# 02_HMS_BW16.net
KiCad netlist of a schematic drawn in Altium Designer
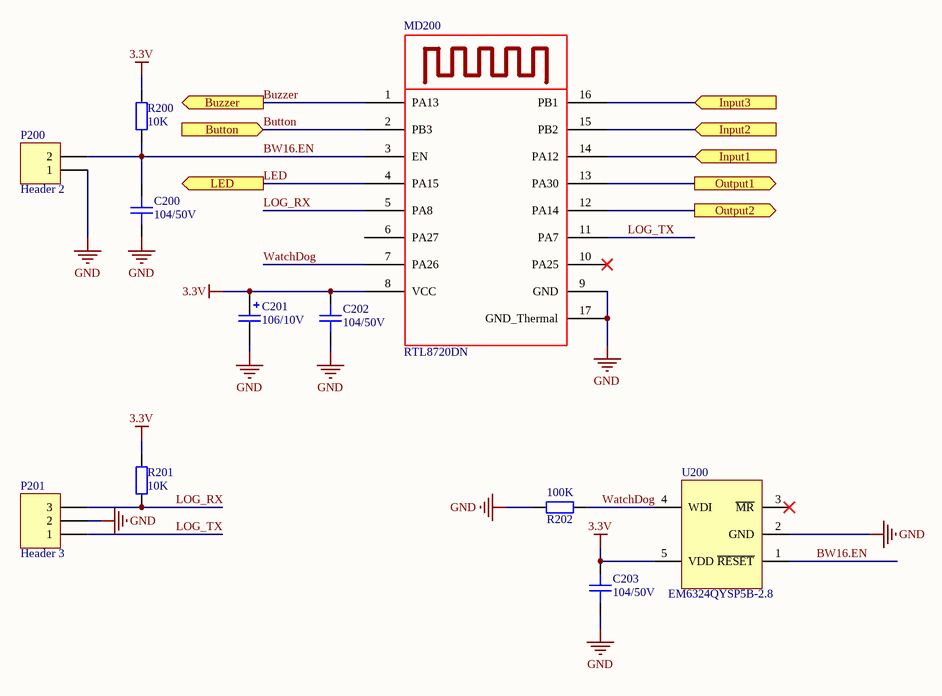
[diagram p0: [02].HMS.BW16.SchDoc]

(export (version "E")
  (design (tool "Eeschema 10.0.6"))
  (components
    (comp (ref "C200")
      (value "104/50V")
      (footprint "CAP_CERAMIC_0402(1005)")
      (description "CAP CER 0.1UF 50V X5R 0402")
      (fields (field (name "MPN") "CC0402KRX5R9BB104") (field (name "MFR") "YAGEO"))
      (libsource (lib "01.Capacitor.0402") (part "CC0402KRX5R9BB104"))
    )
    (comp (ref "C201")
      (value "106/10V")
      (footprint "CAP_TANTAL_1206(3216-18)")
      (description "CAP Tantal 10uF/6.3V 10% 1206")
      (fields (field (name "MPN") "293D106X96R3A2TE3") (field (name "MFR") "KYOCERA AVX Componenis"))
      (libsource (lib "01.Capacitor") (part "TAJC107K010RNJ"))
    )
    (comp (ref "C202")
      (value "104/50V")
      (footprint "CAP_CERAMIC_0402(1005)")
      (description "CAP CER 0.1UF 50V X5R 0402")
      (fields (field (name "MPN") "CC0402KRX5R9BB104") (field (name "MFR") "YAGEO"))
      (libsource (lib "01.Capacitor.0402") (part "CC0402KRX5R9BB104"))
    )
    (comp (ref "C203")
      (value "104/50V")
      (footprint "CAP_CERAMIC_0402(1005)")
      (description "CAP CER 0.1UF 50V X5R 0402")
      (fields (field (name "MPN") "CC0402KRX5R9BB104") (field (name "MFR") "YAGEO"))
      (libsource (lib "01.Capacitor.0402") (part "CC0402KRX5R9BB104"))
    )
    (comp (ref "MD200")
      (value "RTL8720DN")
      (footprint "BW16")
      (description "Module dual wifi 2.4GHz/5.8GHz + BL 5.0")
      (libsource (lib "06.Module") (part "RTL8720DN"))
    )
    (comp (ref "P200")
      (value "Header 2")
      (footprint "HDR1X2")
      (description "Header, 2-Pin")
      (fields (field (name "PUBLISHER") "Altium Limited"))
      (libsource (lib "08.Header") (part "Header 2"))
    )
    (comp (ref "P201")
      (value "Header 3")
      (footprint "HDR1X3")
      (description "Header, 3-Pin")
      (fields (field (name "PUBLISHER") "Altium Limited"))
      (libsource (lib "08.Header") (part "Header 3"))
    )
    (comp (ref "R200")
      (value "10K")
      (footprint "RES_0402(1005)")
      (description "RES 10K OHM 5% 1/8W 0402")
      (fields (field (name "MPN") "RC0402JR-0710KL") (field (name "MFR") "YAGEO"))
      (libsource (lib "") (part "RC0402JR-0710KL_1"))
    )
    (comp (ref "R201")
      (value "10K")
      (footprint "RES_0402(1005)")
      (description "RES 10K OHM 5% 1/8W 0402")
      (fields (field (name "MPN") "RC0402JR-0710KL") (field (name "MFR") "YAGEO"))
      (libsource (lib "") (part "RC0402JR-0710KL_2"))
    )
    (comp (ref "R202")
      (value "100K")
      (footprint "RES_0402(1005)")
      (description "RES 10K OHM 5% 1/8W 0402")
      (fields (field (name "MPN") "RC0402JR-0710KL") (field (name "MFR") "YAGEO"))
      (libsource (lib "02.Resistor.0402") (part "RC0402JR-0710KL"))
    )
    (comp (ref "U200")
      (value "EM6324QYSP5B-2.8")
      (footprint "SOT23-5")
      (description "External watchdog reset")
      (libsource (lib "07.General IC") (part "EM6324QYSP5B"))
    )
  )
  (nets
    (net (code "2") (name "/BW16.EN") (class "Default")
      (node (ref "C200") (pin "1") (pinfunction "1_1") (pintype "passive"))
      (node (ref "MD200") (pin "3") (pinfunction "EN_3") (pintype "passive"))
      (node (ref "P200") (pin "2") (pinfunction "2_2") (pintype "passive"))
      (node (ref "R200") (pin "2") (pinfunction "2_2") (pintype "passive"))
      (node (ref "U200") (pin "1") (pinfunction "~{RESET}_1") (pintype "passive"))
    )
    (net (code "3") (name "/Button") (class "Default")
      (node (ref "MD200") (pin "2") (pinfunction "PB3_2") (pintype "passive"))
    )
    (net (code "4") (name "/Buzzer") (class "Default")
      (node (ref "MD200") (pin "1") (pinfunction "PA13_1") (pintype "passive"))
    )
    (net (code "5") (name "/Input1") (class "Default")
      (node (ref "MD200") (pin "14") (pinfunction "PA12_14") (pintype "passive"))
    )
    (net (code "6") (name "/Input2") (class "Default")
      (node (ref "MD200") (pin "15") (pinfunction "PB2_15") (pintype "passive"))
    )
    (net (code "7") (name "/Input3") (class "Default")
      (node (ref "MD200") (pin "16") (pinfunction "PB1_16") (pintype "passive"))
    )
    (net (code "8") (name "/LED") (class "Default")
      (node (ref "MD200") (pin "4") (pinfunction "PA15_4") (pintype "passive"))
    )
    (net (code "9") (name "/LOG_RX") (class "Default")
      (node (ref "MD200") (pin "5") (pinfunction "PA8_5") (pintype "passive"))
      (node (ref "P201") (pin "3") (pinfunction "3_3") (pintype "passive"))
      (node (ref "R201") (pin "1") (pinfunction "1_1") (pintype "passive"))
    )
    (net (code "10") (name "/LOG_TX") (class "Default")
      (node (ref "MD200") (pin "11") (pinfunction "PA7_11") (pintype "passive"))
      (node (ref "P201") (pin "1") (pinfunction "1_1") (pintype "passive"))
    )
    (net (code "11") (name "/Output1") (class "Default")
      (node (ref "MD200") (pin "13") (pinfunction "PA30_13") (pintype "passive"))
    )
    (net (code "12") (name "/Output2") (class "Default")
      (node (ref "MD200") (pin "12") (pinfunction "PA14_12") (pintype "passive"))
    )
    (net (code "13") (name "/WatchDog") (class "Default")
      (node (ref "MD200") (pin "7") (pinfunction "PA26_7") (pintype "passive"))
      (node (ref "R202") (pin "1") (pinfunction "1_1") (pintype "passive"))
      (node (ref "U200") (pin "4") (pinfunction "WDI_4") (pintype "passive"))
    )
    (net (code "14") (name "3.3V") (class "Default")
      (node (ref "C201") (pin "1") (pinfunction "1_1") (pintype "passive"))
      (node (ref "C202") (pin "1") (pinfunction "1_1") (pintype "passive"))
      (node (ref "C203") (pin "1") (pinfunction "1_1") (pintype "passive"))
      (node (ref "MD200") (pin "8") (pinfunction "VCC_8") (pintype "passive"))
      (node (ref "R200") (pin "1") (pinfunction "1_1") (pintype "passive"))
      (node (ref "R201") (pin "2") (pinfunction "2_2") (pintype "passive"))
      (node (ref "U200") (pin "5") (pinfunction "VDD_5") (pintype "passive"))
    )
    (net (code "15") (name "GND") (class "Default")
      (node (ref "C200") (pin "2") (pinfunction "2_2") (pintype "passive"))
      (node (ref "C201") (pin "2") (pinfunction "2_2") (pintype "passive"))
      (node (ref "C202") (pin "2") (pinfunction "2_2") (pintype "passive"))
      (node (ref "C203") (pin "2") (pinfunction "2_2") (pintype "passive"))
      (node (ref "MD200") (pin "17") (pinfunction "GND_Thermal_17") (pintype "passive"))
      (node (ref "MD200") (pin "9") (pinfunction "GND_9") (pintype "passive"))
      (node (ref "P200") (pin "1") (pinfunction "1_1") (pintype "passive"))
      (node (ref "P201") (pin "2") (pinfunction "2_2") (pintype "passive"))
      (node (ref "R202") (pin "2") (pinfunction "2_2") (pintype "passive"))
      (node (ref "U200") (pin "2") (pinfunction "GND_2") (pintype "passive"))
    )
    (net (code "16") (name "unconnected-(MD200-PA25-Pad10)") (class "Default")
      (node (ref "MD200") (pin "10") (pinfunction "PA25_10") (pintype "passive+no_connect"))
    )
    (net (code "17") (name "unconnected-(MD200-PA27-Pad6)") (class "Default")
      (node (ref "MD200") (pin "6") (pinfunction "PA27_6") (pintype "passive"))
    )
    (net (code "18") (name "unconnected-(U200-~{MR}-Pad3)") (class "Default")
      (node (ref "U200") (pin "3") (pinfunction "~{MR}_3") (pintype "passive+no_connect"))
    )
  )
)
